# VoiceBox.net
KiCad netlist of a schematic drawn in EAGLE
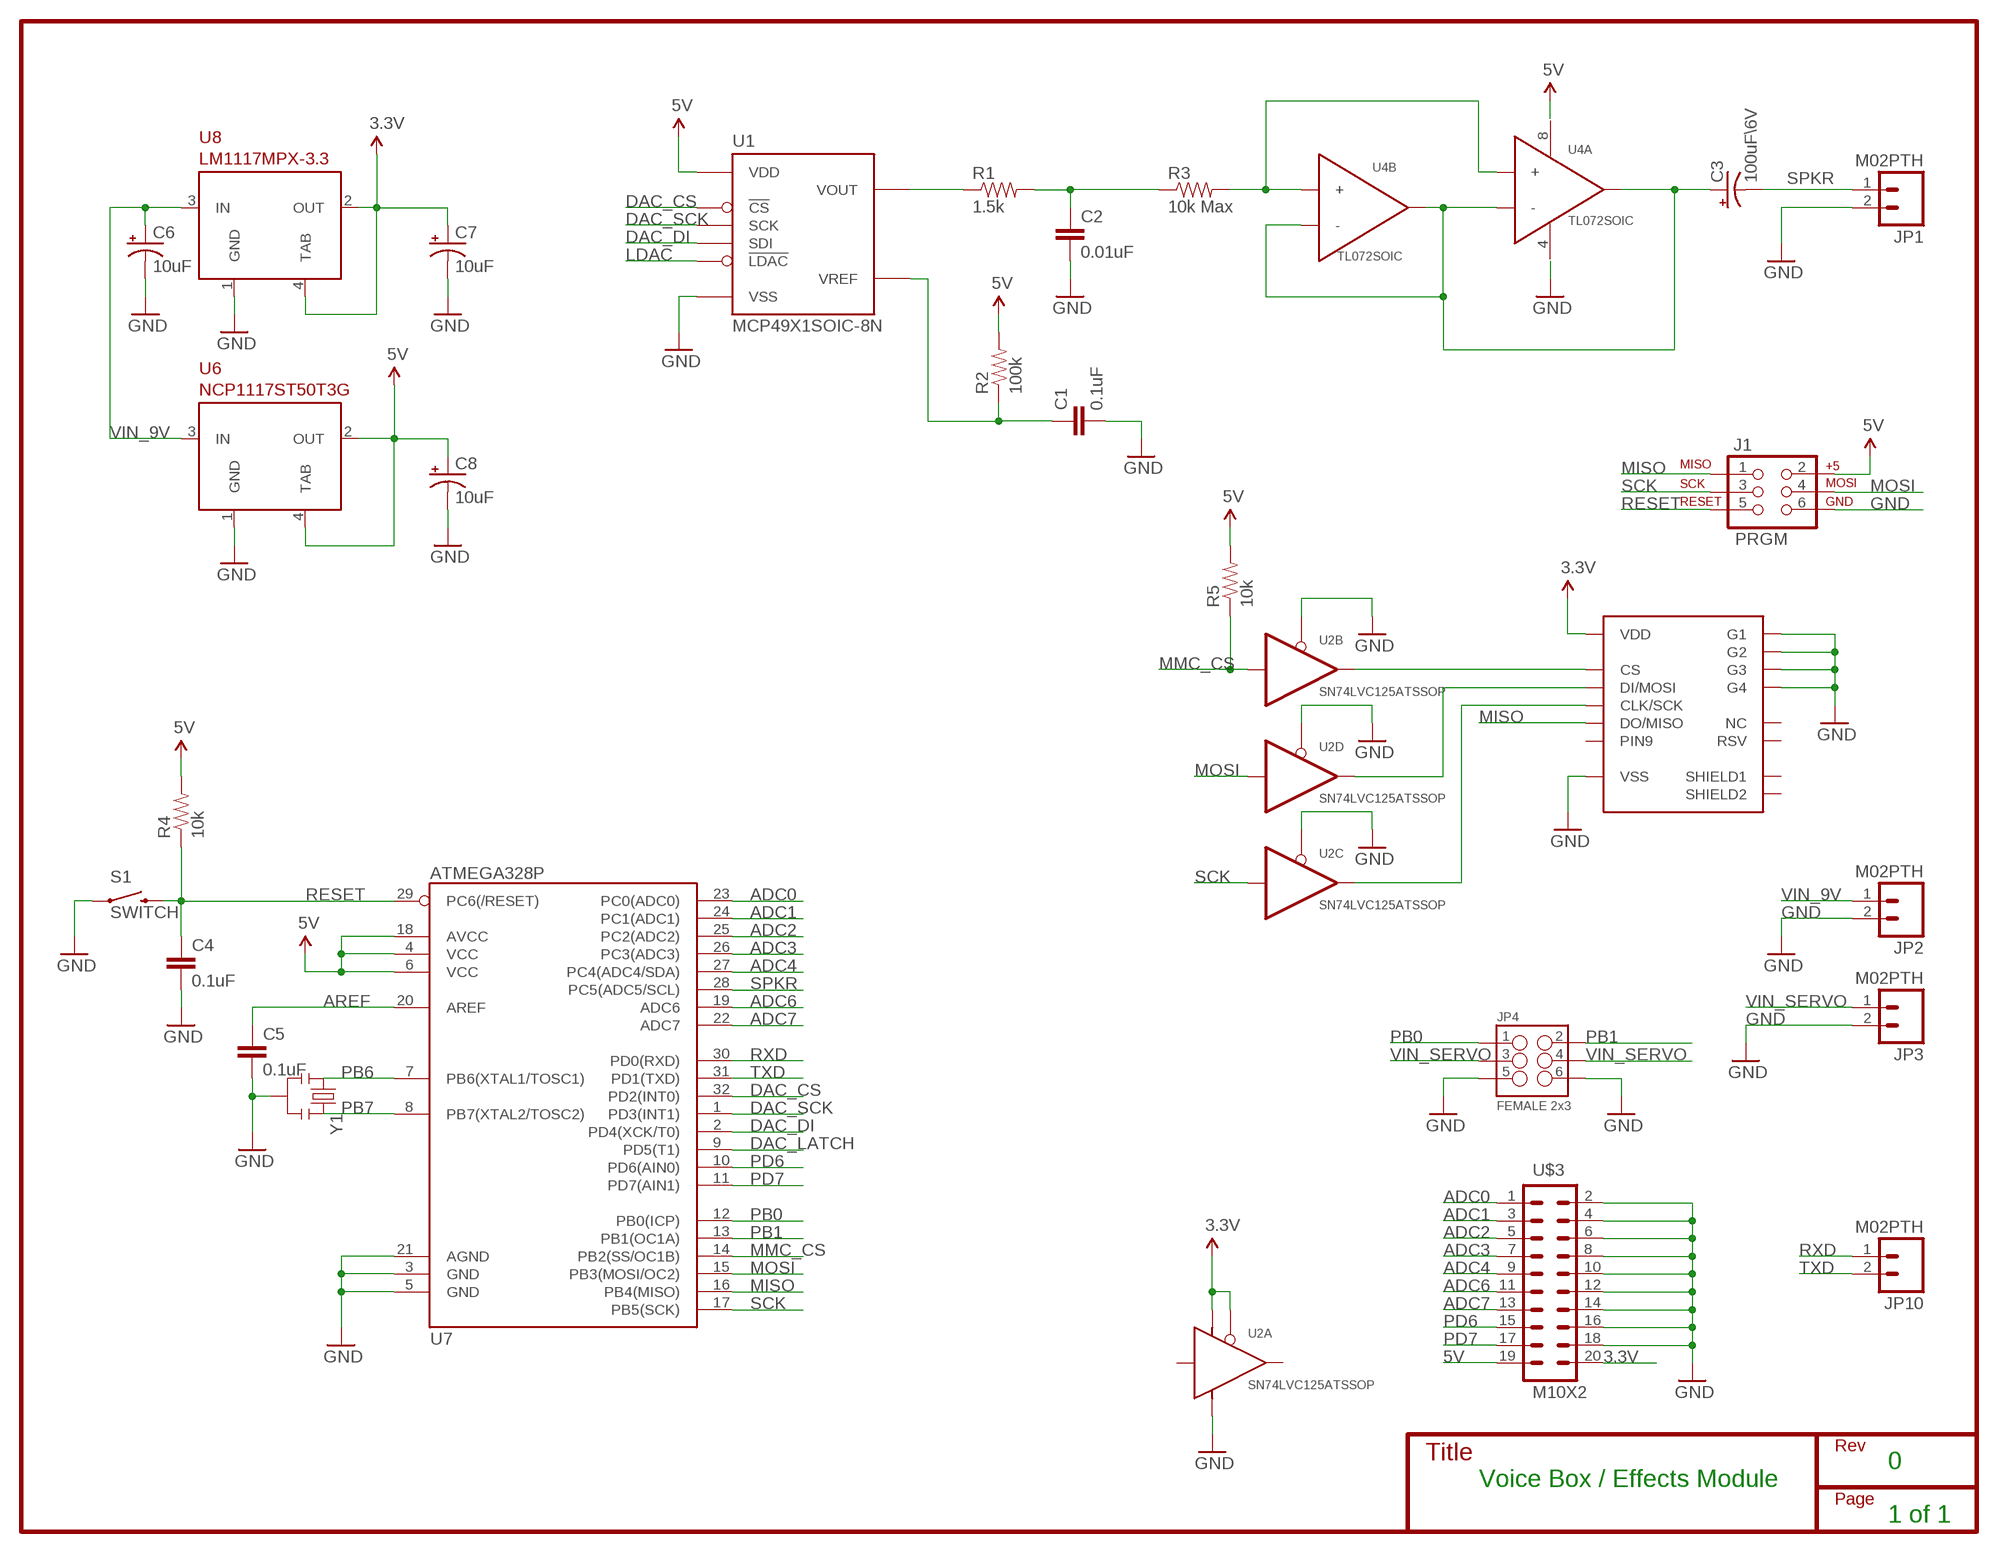
[diagram p0: schematic, sheet 1]

(export (version "E")
  (design (tool "Eeschema 10.0.6"))
  (components
    (comp (ref "C1")
      (value "0.1uF")
      (footprint "eagle-import:0603-CAP")
      (libsource (lib "eagle-import") (part "SparkFun-Passives_CAP0603-CAP"))
    )
    (comp (ref "C2")
      (value "0.01uF")
      (footprint "eagle-import:0603-CAP")
      (libsource (lib "eagle-import") (part "SparkFun-Passives_CAP0603-CAP"))
    )
    (comp (ref "C3")
      (value "100uF\\\\6V")
      (footprint "eagle-import:EIA6032")
      (libsource (lib "eagle-import") (part "CAP_POL6032"))
    )
    (comp (ref "C4")
      (value "0.1uF")
      (footprint "eagle-import:0603-CAP")
      (libsource (lib "eagle-import") (part "CAP0603-CAP"))
    )
    (comp (ref "C5")
      (value "0.1uF")
      (footprint "eagle-import:0603-CAP")
      (libsource (lib "eagle-import") (part "SparkFun-Passives_CAP0603-CAP"))
    )
    (comp (ref "C6")
      (value "10uF")
      (footprint "eagle-import:EIA6032")
      (libsource (lib "eagle-import") (part "CAP_POL6032"))
    )
    (comp (ref "C7")
      (value "10uF")
      (footprint "eagle-import:EIA6032")
      (libsource (lib "eagle-import") (part "CAP_POL6032"))
    )
    (comp (ref "C8")
      (value "10uF")
      (footprint "eagle-import:EIA6032")
      (libsource (lib "eagle-import") (part "CAP_POL6032"))
    )
    (comp (ref "J1")
      (value "PRGM")
      (footprint "eagle-import:2X3")
      (libsource (lib "eagle-import") (part "AVR_SPI_PRG_6PTH"))
    )
    (comp (ref "JP1")
      (value "M02PTH")
      (footprint "eagle-import:1X02")
      (libsource (lib "eagle-import") (part "M02PTH"))
    )
    (comp (ref "JP2")
      (value "M02PTH")
      (footprint "eagle-import:1X02")
      (libsource (lib "eagle-import") (part "M02PTH"))
    )
    (comp (ref "JP3")
      (value "M02PTH")
      (footprint "eagle-import:1X02")
      (libsource (lib "eagle-import") (part "M02PTH"))
    )
    (comp (ref "JP4")
      (value "FEMALE 2x3")
      (footprint "eagle-import:2X3")
      (libsource (lib "eagle-import") (part "M03X2FEMALE"))
    )
    (comp (ref "JP10")
      (value "M02PTH")
      (footprint "eagle-import:1X02")
      (libsource (lib "eagle-import") (part "M02PTH"))
    )
    (comp (ref "R1")
      (value "1.5k")
      (footprint "eagle-import:0603-RES")
      (libsource (lib "eagle-import") (part "RESISTOR0603-RES"))
    )
    (comp (ref "R2")
      (value "100k")
      (footprint "eagle-import:0603-RES")
      (libsource (lib "eagle-import") (part "RESISTOR0603-RES"))
    )
    (comp (ref "R3")
      (value "10k Max")
      (footprint "eagle-import:0603-RES")
      (libsource (lib "eagle-import") (part "RESISTOR0603-RES"))
    )
    (comp (ref "R4")
      (value "10k")
      (footprint "eagle-import:0603-RES")
      (libsource (lib "eagle-import") (part "RESISTOR0603-RES"))
    )
    (comp (ref "R5")
      (value "10k")
      (footprint "eagle-import:0603-RES")
      (libsource (lib "eagle-import") (part "RESISTOR0603-RES"))
    )
    (comp (ref "S1")
      (value "SWITCH")
      (footprint "eagle-import:TACTILE_SWITCH_SMD")
      (libsource (lib "eagle-import") (part "SWITCH-MOMENTARY-2SMD"))
    )
    (comp (ref "U$3")
      (value "M10X2")
      (footprint "eagle-import:2X10")
      (libsource (lib "eagle-import") (part "M10X2"))
    )
    (comp (ref "U1")
      (value "MCP49X1SOIC-8N")
      (footprint "eagle-import:SO08")
      (libsource (lib "eagle-import") (part "MCP49X1SOIC-8N"))
    )
    (comp (ref "U2")
      (value "SN74LVC125ATSSOP")
      (footprint "eagle-import:14-TSSOP")
      (libsource (lib "eagle-import") (part "SN74LVC125ATSSOP"))
    )
    (comp (ref "U3")
      (value "MICROSD_SOCKET")
      (footprint "eagle-import:1932739")
      (fields (field (name "DIGIKEYPART#") "A118085CT-ND"))
      (libsource (lib "eagle-import") (part "MICROSD_SOCKET"))
    )
    (comp (ref "U4")
      (value "TL072SOIC")
      (footprint "eagle-import:SO08")
      (libsource (lib "eagle-import") (part "TL072SOIC"))
    )
    (comp (ref "U6")
      (value "NCP1117ST50T3G")
      (footprint "eagle-import:SOT223")
      (fields (field (name "DIGIKEYPART#") "NCP1117ST50T3GOSCT-ND"))
      (libsource (lib "eagle-import") (part "NCP1117ST50T3G"))
    )
    (comp (ref "U7")
      (value "ATMEGA328P")
      (footprint "eagle-import:TQFP32-08")
      (libsource (lib "eagle-import") (part "ATMEGA328_SMT"))
    )
    (comp (ref "U8")
      (value "LM1117MPX-3.3")
      (footprint "eagle-import:SOT223")
      (fields (field (name "DIGIKEYPART#") "LM1117MPX-3.3/NOPBCT-ND"))
      (libsource (lib "eagle-import") (part "LM1117MPX-3.3"))
    )
    (comp (ref "Y1")
      (value "RESONATORPTH")
      (footprint "eagle-import:RESONATOR-PTH")
      (libsource (lib "eagle-import") (part "RESONATORPTH"))
    )
  )
  (nets
    (net (code "1") (name "/4") (class "Default")
      (node (ref "U4") (pin "4") (pinfunction "4_4") (pintype "power_in"))
    )
    (net (code "2") (name "/8") (class "Default")
      (node (ref "U4") (pin "8") (pinfunction "8_8") (pintype "power_in"))
    )
    (net (code "3") (name "/ADC0") (class "Default")
      (node (ref "U$3") (pin "1") (pinfunction "1_1") (pintype "passive"))
      (node (ref "U7") (pin "23") (pinfunction "PC0(ADC0)_23") (pintype "bidirectional"))
    )
    (net (code "4") (name "/ADC1") (class "Default")
      (node (ref "U$3") (pin "3") (pinfunction "3_3") (pintype "passive"))
      (node (ref "U7") (pin "24") (pinfunction "PC1(ADC1)_24") (pintype "bidirectional"))
    )
    (net (code "5") (name "/ADC2") (class "Default")
      (node (ref "U$3") (pin "5") (pinfunction "5_5") (pintype "passive"))
      (node (ref "U7") (pin "25") (pinfunction "PC2(ADC2)_25") (pintype "bidirectional"))
    )
    (net (code "6") (name "/ADC3") (class "Default")
      (node (ref "U$3") (pin "7") (pinfunction "7_7") (pintype "passive"))
      (node (ref "U7") (pin "26") (pinfunction "PC3(ADC3)_26") (pintype "bidirectional"))
    )
    (net (code "7") (name "/ADC4") (class "Default")
      (node (ref "U$3") (pin "9") (pinfunction "9_9") (pintype "passive"))
      (node (ref "U7") (pin "27") (pinfunction "PC4(ADC4/SDA)_27") (pintype "bidirectional"))
    )
    (net (code "8") (name "/ADC6") (class "Default")
      (node (ref "U$3") (pin "11") (pinfunction "11_11") (pintype "passive"))
      (node (ref "U7") (pin "19") (pinfunction "ADC6_19") (pintype "bidirectional"))
    )
    (net (code "9") (name "/ADC7") (class "Default")
      (node (ref "U$3") (pin "13") (pinfunction "13_13") (pintype "passive"))
      (node (ref "U7") (pin "22") (pinfunction "ADC7_22") (pintype "bidirectional"))
    )
    (net (code "10") (name "/AREF") (class "Default")
      (node (ref "C5") (pin "1") (pinfunction "1_1") (pintype "passive"))
      (node (ref "U7") (pin "20") (pinfunction "AREF_20") (pintype "bidirectional"))
    )
    (net (code "11") (name "/DAC_CS") (class "Default")
      (node (ref "U1") (pin "2") (pinfunction "~{CS}_2") (pintype "bidirectional"))
      (node (ref "U7") (pin "32") (pinfunction "PD2(INT0)_32") (pintype "bidirectional"))
    )
    (net (code "12") (name "/DAC_DI") (class "Default")
      (node (ref "U1") (pin "4") (pinfunction "SDI_4") (pintype "bidirectional"))
      (node (ref "U7") (pin "2") (pinfunction "PD4(XCK/T0)_2") (pintype "bidirectional"))
    )
    (net (code "13") (name "/DAC_LATCH") (class "Default")
      (node (ref "U7") (pin "9") (pinfunction "PD5(T1)_9") (pintype "bidirectional"))
    )
    (net (code "14") (name "/DAC_SCK") (class "Default")
      (node (ref "U1") (pin "3") (pinfunction "SCK_3") (pintype "bidirectional"))
      (node (ref "U7") (pin "1") (pinfunction "PD3(INT1)_1") (pintype "bidirectional"))
    )
    (net (code "15") (name "/LDAC") (class "Default")
      (node (ref "U1") (pin "5") (pinfunction "~{LDAC}_5") (pintype "bidirectional"))
    )
    (net (code "16") (name "/MISO") (class "Default")
      (node (ref "J1") (pin "1") (pinfunction "1_1") (pintype "passive"))
      (node (ref "U3") (pin "7") (pinfunction "DO/MISO_7") (pintype "bidirectional"))
      (node (ref "U7") (pin "16") (pinfunction "PB4(MISO)_16") (pintype "bidirectional"))
    )
    (net (code "17") (name "/MMC_CS") (class "Default")
      (node (ref "R5") (pin "1") (pinfunction "1_1") (pintype "passive"))
      (node (ref "U2") (pin "5") (pinfunction "IN_5") (pintype "input"))
      (node (ref "U7") (pin "14") (pinfunction "PB2(SS/OC1B)_14") (pintype "bidirectional"))
    )
    (net (code "18") (name "/MOSI") (class "Default")
      (node (ref "J1") (pin "4") (pinfunction "4_4") (pintype "passive"))
      (node (ref "U2") (pin "12") (pinfunction "IN_12") (pintype "input"))
      (node (ref "U7") (pin "15") (pinfunction "PB3(MOSI/OC2)_15") (pintype "bidirectional"))
    )
    (net (code "19") (name "/PB0") (class "Default")
      (node (ref "JP4") (pin "1") (pinfunction "1_1") (pintype "bidirectional"))
      (node (ref "U7") (pin "12") (pinfunction "PB0(ICP)_12") (pintype "bidirectional"))
    )
    (net (code "20") (name "/PB1") (class "Default")
      (node (ref "JP4") (pin "2") (pinfunction "2_2") (pintype "bidirectional"))
      (node (ref "U7") (pin "13") (pinfunction "PB1(OC1A)_13") (pintype "bidirectional"))
    )
    (net (code "21") (name "/PB6") (class "Default")
      (node (ref "U7") (pin "7") (pinfunction "PB6(XTAL1/TOSC1)_7") (pintype "bidirectional"))
      (node (ref "Y1") (pin "1") (pinfunction "1_1") (pintype "passive"))
    )
    (net (code "22") (name "/PB7") (class "Default")
      (node (ref "U7") (pin "8") (pinfunction "PB7(XTAL2/TOSC2)_8") (pintype "bidirectional"))
      (node (ref "Y1") (pin "3") (pinfunction "3_3") (pintype "passive"))
    )
    (net (code "23") (name "/PD6") (class "Default")
      (node (ref "U$3") (pin "15") (pinfunction "15_15") (pintype "passive"))
      (node (ref "U7") (pin "10") (pinfunction "PD6(AIN0)_10") (pintype "bidirectional"))
    )
    (net (code "24") (name "/PD7") (class "Default")
      (node (ref "U$3") (pin "17") (pinfunction "17_17") (pintype "passive"))
      (node (ref "U7") (pin "11") (pinfunction "PD7(AIN1)_11") (pintype "bidirectional"))
    )
    (net (code "25") (name "/RESET") (class "Default")
      (node (ref "C4") (pin "1") (pinfunction "1_1") (pintype "passive"))
      (node (ref "J1") (pin "5") (pinfunction "5_5") (pintype "passive"))
      (node (ref "R4") (pin "1") (pinfunction "1_1") (pintype "passive"))
      (node (ref "S1") (pin "3") (pinfunction "2_3") (pintype "passive"))
      (node (ref "U7") (pin "29") (pinfunction "PC6(/RESET)_29") (pintype "bidirectional"))
    )
    (net (code "26") (name "/RXD") (class "Default")
      (node (ref "JP10") (pin "1") (pinfunction "1_1") (pintype "passive"))
      (node (ref "U7") (pin "30") (pinfunction "PD0(RXD)_30") (pintype "bidirectional"))
    )
    (net (code "27") (name "/SCK") (class "Default")
      (node (ref "J1") (pin "3") (pinfunction "3_3") (pintype "passive"))
      (node (ref "U2") (pin "9") (pinfunction "IN_9") (pintype "input"))
      (node (ref "U7") (pin "17") (pinfunction "PB5(SCK)_17") (pintype "bidirectional"))
    )
    (net (code "28") (name "/SPKR") (class "Default")
      (node (ref "C3") (pin "P$2") (pinfunction "-_P$2") (pintype "passive"))
      (node (ref "JP1") (pin "1") (pinfunction "1_1") (pintype "passive"))
      (node (ref "U7") (pin "28") (pinfunction "PC5(ADC5/SCL)_28") (pintype "bidirectional"))
    )
    (net (code "29") (name "/TXD") (class "Default")
      (node (ref "JP10") (pin "2") (pinfunction "2_2") (pintype "passive"))
      (node (ref "U7") (pin "31") (pinfunction "PD1(TXD)_31") (pintype "bidirectional"))
    )
    (net (code "30") (name "/VIN_9V") (class "Default")
      (node (ref "C6") (pin "P$1") (pinfunction "+_P$1") (pintype "passive"))
      (node (ref "JP2") (pin "1") (pinfunction "1_1") (pintype "passive"))
      (node (ref "U6") (pin "3") (pinfunction "IN_3") (pintype "bidirectional"))
      (node (ref "U8") (pin "3") (pinfunction "IN_3") (pintype "bidirectional"))
    )
    (net (code "31") (name "/VIN_SERVO") (class "Default")
      (node (ref "JP3") (pin "1") (pinfunction "1_1") (pintype "passive"))
      (node (ref "JP4") (pin "3") (pinfunction "3_3") (pintype "bidirectional"))
      (node (ref "JP4") (pin "4") (pinfunction "4_4") (pintype "bidirectional"))
    )
    (net (code "32") (name "3.3V") (class "Default")
      (node (ref "C7") (pin "P$1") (pinfunction "+_P$1") (pintype "passive"))
      (node (ref "U$3") (pin "20") (pinfunction "20_20") (pintype "passive"))
      (node (ref "U2") (pin "1") (pinfunction "~{OE}_1") (pintype "input"))
      (node (ref "U2") (pin "14") (pinfunction "VCC_14") (pintype "power_in"))
      (node (ref "U3") (pin "4") (pinfunction "VDD_4") (pintype "bidirectional"))
      (node (ref "U8") (pin "2") (pinfunction "OUT_2") (pintype "bidirectional"))
      (node (ref "U8") (pin "4") (pinfunction "TAB_4") (pintype "bidirectional"))
    )
    (net (code "33") (name "5V") (class "Default")
      (node (ref "C8") (pin "P$1") (pinfunction "+_P$1") (pintype "passive"))
      (node (ref "J1") (pin "2") (pinfunction "2_2") (pintype "passive"))
      (node (ref "R2") (pin "2") (pinfunction "2_2") (pintype "passive"))
      (node (ref "R4") (pin "2") (pinfunction "2_2") (pintype "passive"))
      (node (ref "R5") (pin "2") (pinfunction "2_2") (pintype "passive"))
      (node (ref "U$3") (pin "19") (pinfunction "19_19") (pintype "passive"))
      (node (ref "U1") (pin "1") (pinfunction "VDD_1") (pintype "bidirectional"))
      (node (ref "U6") (pin "2") (pinfunction "OUT_2") (pintype "bidirectional"))
      (node (ref "U6") (pin "4") (pinfunction "TAB_4") (pintype "bidirectional"))
      (node (ref "U7") (pin "18") (pinfunction "AVCC_18") (pintype "bidirectional"))
      (node (ref "U7") (pin "4") (pinfunction "VCC_4") (pintype "bidirectional"))
      (node (ref "U7") (pin "6") (pinfunction "VCC_6") (pintype "bidirectional"))
    )
    (net (code "34") (name "GND") (class "Default")
      (node (ref "C1") (pin "2") (pinfunction "2_2") (pintype "passive"))
      (node (ref "C2") (pin "2") (pinfunction "2_2") (pintype "passive"))
      (node (ref "C4") (pin "2") (pinfunction "2_2") (pintype "passive"))
      (node (ref "C5") (pin "2") (pinfunction "2_2") (pintype "passive"))
      (node (ref "C6") (pin "P$2") (pinfunction "-_P$2") (pintype "passive"))
      (node (ref "C7") (pin "P$2") (pinfunction "-_P$2") (pintype "passive"))
      (node (ref "C8") (pin "P$2") (pinfunction "-_P$2") (pintype "passive"))
      (node (ref "J1") (pin "6") (pinfunction "6_6") (pintype "passive"))
      (node (ref "JP1") (pin "2") (pinfunction "2_2") (pintype "passive"))
      (node (ref "JP2") (pin "2") (pinfunction "2_2") (pintype "passive"))
      (node (ref "JP3") (pin "2") (pinfunction "2_2") (pintype "passive"))
      (node (ref "JP4") (pin "5") (pinfunction "5_5") (pintype "bidirectional"))
      (node (ref "JP4") (pin "6") (pinfunction "6_6") (pintype "bidirectional"))
      (node (ref "S1") (pin "1") (pinfunction "1_1") (pintype "passive"))
      (node (ref "U$3") (pin "10") (pinfunction "10_10") (pintype "passive"))
      (node (ref "U$3") (pin "12") (pinfunction "12_12") (pintype "passive"))
      (node (ref "U$3") (pin "14") (pinfunction "14_14") (pintype "passive"))
      (node (ref "U$3") (pin "16") (pinfunction "16_16") (pintype "passive"))
      (node (ref "U$3") (pin "18") (pinfunction "18_18") (pintype "passive"))
      (node (ref "U$3") (pin "2") (pinfunction "2_2") (pintype "passive"))
      (node (ref "U$3") (pin "4") (pinfunction "4_4") (pintype "passive"))
      (node (ref "U$3") (pin "6") (pinfunction "6_6") (pintype "passive"))
      (node (ref "U$3") (pin "8") (pinfunction "8_8") (pintype "passive"))
      (node (ref "U1") (pin "7") (pinfunction "VSS_7") (pintype "bidirectional"))
      (node (ref "U2") (pin "10") (pinfunction "~{OE}_10") (pintype "input"))
      (node (ref "U2") (pin "13") (pinfunction "~{OE}_13") (pintype "input"))
      (node (ref "U2") (pin "4") (pinfunction "~{OE}_4") (pintype "input"))
      (node (ref "U2") (pin "7") (pinfunction "GND_7") (pintype "power_in"))
      (node (ref "U3") (pin "6") (pinfunction "VSS_6") (pintype "bidirectional"))
      (node (ref "U3") (pin "G1") (pinfunction "G1_G1") (pintype "bidirectional"))
      (node (ref "U3") (pin "G2") (pinfunction "G2_G2") (pintype "bidirectional"))
      (node (ref "U3") (pin "G3") (pinfunction "G3_G3") (pintype "bidirectional"))
      (node (ref "U3") (pin "G4") (pinfunction "G4_G4") (pintype "bidirectional"))
      (node (ref "U6") (pin "1") (pinfunction "GND_1") (pintype "bidirectional"))
      (node (ref "U7") (pin "21") (pinfunction "AGND_21") (pintype "bidirectional"))
      (node (ref "U7") (pin "3") (pinfunction "GND_3") (pintype "bidirectional"))
      (node (ref "U7") (pin "5") (pinfunction "GND_5") (pintype "bidirectional"))
      (node (ref "U8") (pin "1") (pinfunction "GND_1") (pintype "bidirectional"))
      (node (ref "Y1") (pin "2") (pinfunction "2_2") (pintype "passive"))
    )
    (net (code "35") (name "Net-(C2-Pad1)") (class "Default")
      (node (ref "C2") (pin "1") (pinfunction "1_1") (pintype "passive"))
      (node (ref "R1") (pin "2") (pinfunction "2_2") (pintype "passive"))
      (node (ref "R3") (pin "1") (pinfunction "1_1") (pintype "passive"))
    )
    (net (code "36") (name "Net-(C3-+)") (class "Default")
      (node (ref "C3") (pin "P$1") (pinfunction "+_P$1") (pintype "passive"))
      (node (ref "U4") (pin "1") (pinfunction "OUT_1") (pintype "output"))
      (node (ref "U4") (pin "2") (pinfunction "-_2") (pintype "input"))
      (node (ref "U4") (pin "6") (pinfunction "-_6") (pintype "input"))
      (node (ref "U4") (pin "7") (pinfunction "OUT_7") (pintype "output"))
    )
    (net (code "37") (name "Net-(U1-VOUT)") (class "Default")
      (node (ref "R1") (pin "1") (pinfunction "1_1") (pintype "passive"))
      (node (ref "U1") (pin "8") (pinfunction "VOUT_8") (pintype "bidirectional"))
    )
    (net (code "38") (name "Net-(U1-VREF)") (class "Default")
      (node (ref "C1") (pin "1") (pinfunction "1_1") (pintype "passive"))
      (node (ref "R2") (pin "1") (pinfunction "1_1") (pintype "passive"))
      (node (ref "U1") (pin "6") (pinfunction "VREF_6") (pintype "bidirectional"))
    )
    (net (code "39") (name "Net-(U2B-OUT)") (class "Default")
      (node (ref "U2") (pin "6") (pinfunction "OUT_6") (pintype "output"))
      (node (ref "U3") (pin "2") (pinfunction "CS_2") (pintype "bidirectional"))
    )
    (net (code "40") (name "Net-(U2C-OUT)") (class "Default")
      (node (ref "U2") (pin "8") (pinfunction "OUT_8") (pintype "output"))
      (node (ref "U3") (pin "5") (pinfunction "CLK/SCK_5") (pintype "bidirectional"))
    )
    (net (code "41") (name "Net-(U2D-OUT)") (class "Default")
      (node (ref "U2") (pin "11") (pinfunction "OUT_11") (pintype "output"))
      (node (ref "U3") (pin "3") (pinfunction "DI/MOSI_3") (pintype "bidirectional"))
    )
    (net (code "42") (name "Net-(U4A-+)") (class "Default")
      (node (ref "R3") (pin "2") (pinfunction "2_2") (pintype "passive"))
      (node (ref "U4") (pin "3") (pinfunction "+_3") (pintype "input"))
      (node (ref "U4") (pin "5") (pinfunction "+_5") (pintype "input"))
    )
    (net (code "43") (name "unconnected-(U2A-IN-Pad2)") (class "Default")
      (node (ref "U2") (pin "2") (pinfunction "IN_2") (pintype "input"))
    )
    (net (code "44") (name "unconnected-(U2A-OUT-Pad3)") (class "Default")
      (node (ref "U2") (pin "3") (pinfunction "OUT_3") (pintype "output"))
    )
    (net (code "45") (name "unconnected-(U3-NC-Pad1)") (class "Default")
      (node (ref "U3") (pin "1") (pinfunction "NC_1") (pintype "bidirectional"))
    )
    (net (code "46") (name "unconnected-(U3-PIN9-Pad9)") (class "Default")
      (node (ref "U3") (pin "9") (pinfunction "PIN9_9") (pintype "bidirectional"))
    )
    (net (code "47") (name "unconnected-(U3-PadSHIELD1)") (class "Default")
      (node (ref "U3") (pin "SHIELD1") (pinfunction "SHIELD1_SHIELD1") (pintype "bidirectional"))
    )
    (net (code "48") (name "unconnected-(U3-PadSHIELD2)") (class "Default")
      (node (ref "U3") (pin "SHIELD2") (pinfunction "SHIELD2_SHIELD2") (pintype "bidirectional"))
    )
    (net (code "49") (name "unconnected-(U3-RSV-Pad8)") (class "Default")
      (node (ref "U3") (pin "8") (pinfunction "RSV_8") (pintype "bidirectional"))
    )
  )
)
